# Bias_Lighting_Controller_Schematic.net
KiCad netlist of a schematic drawn in EAGLE
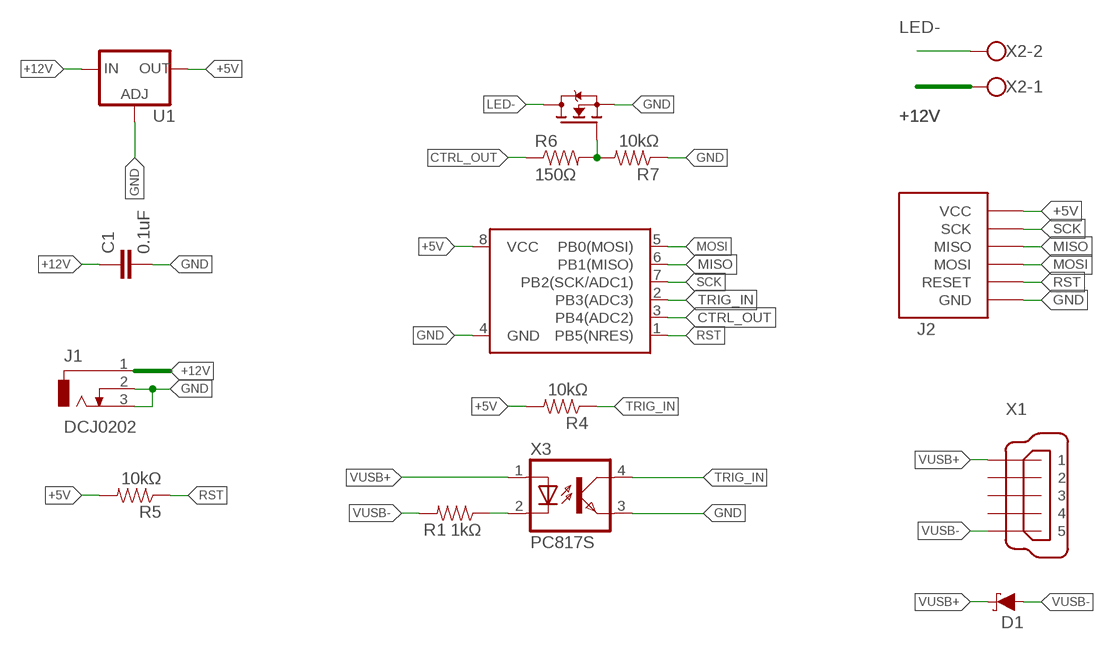
[diagram p0: schematic, sheet 1]

(export (version "E")
  (design (tool "Eeschema 10.0.6"))
  (components
    (comp (ref "ATTINY85")
      (value "ATTINY45")
      (footprint "eagle-import:SO08-EIAJ")
      (libsource (lib "eagle-import") (part "ATTINY45"))
    )
    (comp (ref "C1")
      (value "0.1uF")
      (footprint "eagle-import:C1206K")
      (libsource (lib "eagle-import") (part "C-EUC1206K"))
    )
    (comp (ref "D1")
      (value "DIODE-SCHOTTKY-SS14")
      (footprint "eagle-import:SMA-DIODE")
      (libsource (lib "eagle-import") (part "DIODE-SCHOTTKY-SS14"))
    )
    (comp (ref "IRF740_MOSFET1")
      (value "MOSFET-N-SOT23")
      (footprint "eagle-import:SOT23")
      (libsource (lib "eagle-import") (part "MOSFET-N-SOT23"))
    )
    (comp (ref "J1")
      (value "DCJ0202")
      (footprint "eagle-import:DCJ0202")
      (libsource (lib "eagle-import") (part "DCJ0202"))
    )
    (comp (ref "J2")
      (value "AVR_MICRO_ICP")
      (footprint "eagle-import:AVR_MICRO_ICP")
      (libsource (lib "eagle-import") (part "AVR_MICRO_ICP"))
    )
    (comp (ref "R1")
      (value "1kΩ")
      (footprint "eagle-import:1206")
      (libsource (lib "eagle-import") (part "RESISTOR1206"))
    )
    (comp (ref "R4")
      (value "10kΩ")
      (footprint "eagle-import:1206")
      (libsource (lib "eagle-import") (part "RESISTOR1206"))
    )
    (comp (ref "R5")
      (value "10kΩ")
      (footprint "eagle-import:1206")
      (libsource (lib "eagle-import") (part "RESISTOR1206"))
    )
    (comp (ref "R6")
      (value "150Ω")
      (footprint "eagle-import:1206")
      (libsource (lib "eagle-import") (part "RESISTOR1206"))
    )
    (comp (ref "R7")
      (value "10kΩ")
      (footprint "eagle-import:1206")
      (libsource (lib "eagle-import") (part "RESISTOR1206"))
    )
    (comp (ref "U1")
      (value "V_REG_317SMD")
      (footprint "eagle-import:SOT223")
      (libsource (lib "eagle-import") (part "V_REG_317SMD"))
    )
    (comp (ref "X1")
      (value "MINI-USB-UX60-MB-5ST")
      (footprint "eagle-import:UX60-MB-5ST")
      (libsource (lib "eagle-import") (part "MINI-USB-UX60-MB-5ST"))
    )
    (comp (ref "X2")
      (value "W237-102")
      (footprint "eagle-import:W237-102")
      (fields (field (name "MPN") "237-102"))
      (libsource (lib "eagle-import") (part "W237-102"))
    )
    (comp (ref "X3")
      (value "PC817S")
      (footprint "eagle-import:PC817SMT")
      (libsource (lib "eagle-import") (part "PC817S"))
    )
  )
  (nets
    (net (code "1") (name "+5V") (class "Default")
      (node (ref "ATTINY85") (pin "8") (pinfunction "VCC_8") (pintype "bidirectional"))
      (node (ref "J2") (pin "VCC") (pinfunction "VCC_VCC") (pintype "power_in"))
      (node (ref "R4") (pin "2") (pinfunction "2_2") (pintype "passive"))
      (node (ref "R5") (pin "2") (pinfunction "2_2") (pintype "passive"))
      (node (ref "U1") (pin "2") (pinfunction "OUT_2") (pintype "output"))
    )
    (net (code "2") (name "+12V") (class "Default")
      (node (ref "C1") (pin "1") (pinfunction "1_1") (pintype "passive"))
      (node (ref "J1") (pin "1") (pinfunction "1_1") (pintype "passive"))
      (node (ref "U1") (pin "3") (pinfunction "IN_3") (pintype "input"))
      (node (ref "X2") (pin "1") (pinfunction "KL_1") (pintype "passive"))
    )
    (net (code "3") (name "CTRL_OUT") (class "Default")
      (node (ref "ATTINY85") (pin "3") (pinfunction "PB4(ADC2)_3") (pintype "bidirectional"))
      (node (ref "R6") (pin "1") (pinfunction "1_1") (pintype "passive"))
    )
    (net (code "4") (name "GND") (class "Default")
      (node (ref "ATTINY85") (pin "4") (pinfunction "GND_4") (pintype "bidirectional"))
      (node (ref "C1") (pin "2") (pinfunction "2_2") (pintype "passive"))
      (node (ref "IRF740_MOSFET1") (pin "2") (pinfunction "S_2") (pintype "passive"))
      (node (ref "J1") (pin "2") (pinfunction "2_2") (pintype "passive"))
      (node (ref "J1") (pin "3") (pinfunction "3_3") (pintype "passive"))
      (node (ref "J2") (pin "GND") (pinfunction "GND_GND") (pintype "power_in"))
      (node (ref "R7") (pin "1") (pinfunction "1_1") (pintype "passive"))
      (node (ref "U1") (pin "1") (pinfunction "ADJ_1") (pintype "input"))
      (node (ref "X3") (pin "3") (pinfunction "EMIT_3") (pintype "passive"))
    )
    (net (code "5") (name "LED-") (class "Default")
      (node (ref "IRF740_MOSFET1") (pin "3") (pinfunction "D_3") (pintype "passive"))
      (node (ref "X2") (pin "2") (pinfunction "KL_2") (pintype "passive"))
    )
    (net (code "6") (name "MISO") (class "Default")
      (node (ref "ATTINY85") (pin "6") (pinfunction "PB1(MISO)_6") (pintype "bidirectional"))
      (node (ref "J2") (pin "MISO") (pinfunction "MISO_MISO") (pintype "bidirectional"))
    )
    (net (code "7") (name "MOSI") (class "Default")
      (node (ref "ATTINY85") (pin "5") (pinfunction "PB0(MOSI)_5") (pintype "bidirectional"))
      (node (ref "J2") (pin "MOSI") (pinfunction "MOSI_MOSI") (pintype "bidirectional"))
    )
    (net (code "8") (name "Net-(IRF740_MOSFET1-G)") (class "Default")
      (node (ref "IRF740_MOSFET1") (pin "1") (pinfunction "G_1") (pintype "passive"))
      (node (ref "R6") (pin "2") (pinfunction "2_2") (pintype "passive"))
      (node (ref "R7") (pin "2") (pinfunction "2_2") (pintype "passive"))
    )
    (net (code "9") (name "Net-(X3-C)") (class "Default")
      (node (ref "R1") (pin "1") (pinfunction "1_1") (pintype "passive"))
      (node (ref "X3") (pin "2") (pinfunction "C_2") (pintype "passive"))
    )
    (net (code "10") (name "RST") (class "Default")
      (node (ref "ATTINY85") (pin "1") (pinfunction "PB5(NRES)_1") (pintype "bidirectional"))
      (node (ref "J2") (pin "RESET") (pinfunction "RESET_RESET") (pintype "bidirectional"))
      (node (ref "R5") (pin "1") (pinfunction "1_1") (pintype "passive"))
    )
    (net (code "11") (name "SCK") (class "Default")
      (node (ref "ATTINY85") (pin "7") (pinfunction "PB2(SCK/ADC1)_7") (pintype "bidirectional"))
      (node (ref "J2") (pin "SCK") (pinfunction "SCK_SCK") (pintype "bidirectional"))
    )
    (net (code "12") (name "TRIG_IN") (class "Default")
      (node (ref "ATTINY85") (pin "2") (pinfunction "PB3(ADC3)_2") (pintype "bidirectional"))
      (node (ref "R4") (pin "1") (pinfunction "1_1") (pintype "passive"))
      (node (ref "X3") (pin "4") (pinfunction "COL_4") (pintype "passive"))
    )
    (net (code "13") (name "VUSB+") (class "Default")
      (node (ref "D1") (pin "C") (pinfunction "C_C") (pintype "passive"))
      (node (ref "X1") (pin "1") (pinfunction "1_1") (pintype "input"))
      (node (ref "X3") (pin "1") (pinfunction "A_1") (pintype "passive"))
    )
    (net (code "14") (name "VUSB-") (class "Default")
      (node (ref "D1") (pin "A") (pinfunction "A_A") (pintype "passive"))
      (node (ref "R1") (pin "2") (pinfunction "2_2") (pintype "passive"))
      (node (ref "X1") (pin "5") (pinfunction "5_5") (pintype "input"))
    )
    (net (code "15") (name "unconnected-(X1-Pad2)") (class "Default")
      (node (ref "X1") (pin "2") (pinfunction "2_2") (pintype "input"))
    )
    (net (code "16") (name "unconnected-(X1-Pad3)") (class "Default")
      (node (ref "X1") (pin "3") (pinfunction "3_3") (pintype "input"))
    )
    (net (code "17") (name "unconnected-(X1-Pad4)") (class "Default")
      (node (ref "X1") (pin "4") (pinfunction "4_4") (pintype "input"))
    )
  )
)
